# RS485_MODBUS.net
KiCad netlist of a schematic drawn in Altium Designer
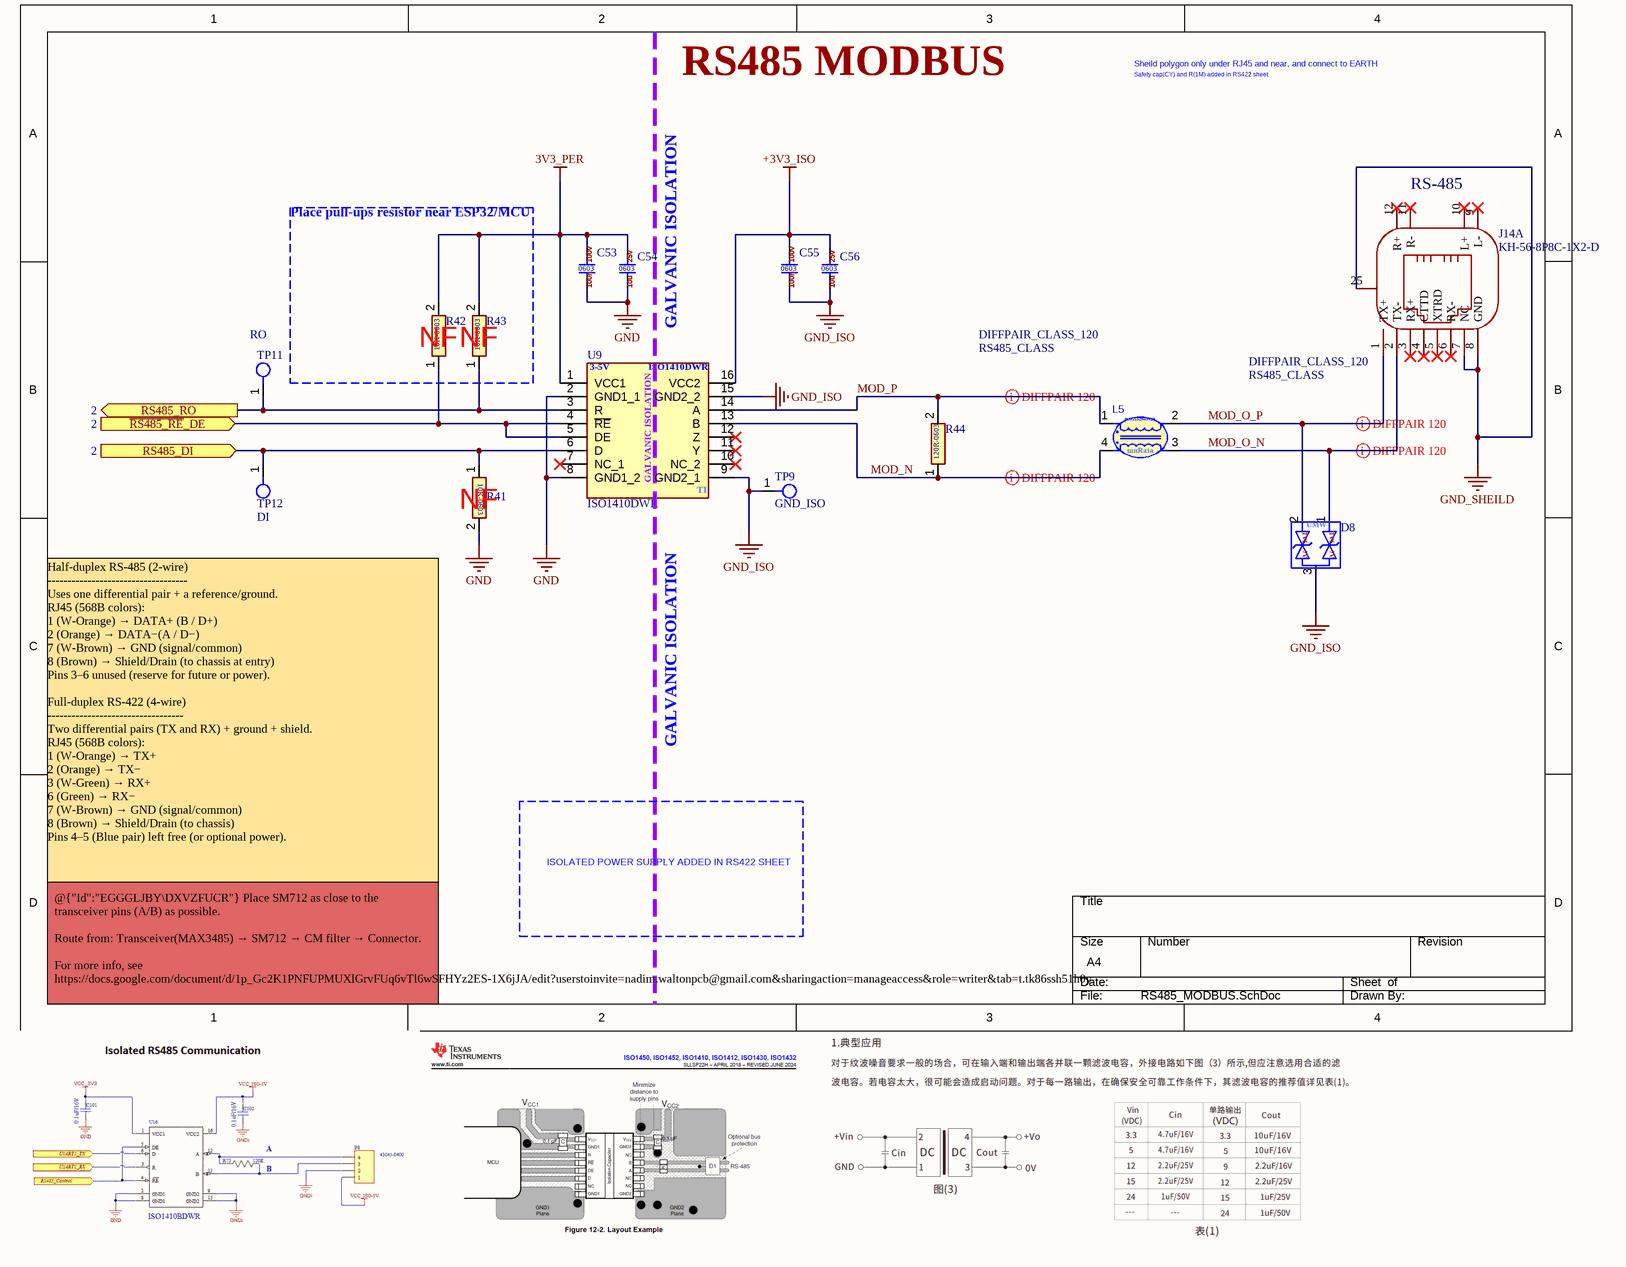
[diagram p0: RS485_MODBUS.SchDoc]

(export (version "E")
  (design (tool "Eeschema 10.0.6"))
  (components
    (comp (ref "C53")
      (value "CL10B104KC8NNNC")
      (footprint "0603-CAP")
      (description "CAP: CER 100NF 100V X7R 0603")
      (fields (field (name "LCSC PART #") "C15725"))
      (libsource (lib "Nadim Altium Lib-Univ") (part "CL10B104KC8NNNC"))
    )
    (comp (ref "C54")
      (value "CL10A106MA8NRNC")
      (footprint "0603-CAP")
      (description "CAP: CER 10UF 25V X5R 0603")
      (fields (field (name "LCSC PART #") "C96446"))
      (libsource (lib "Nadim Altium Lib-Univ") (part "CL10A106MA8NRNC"))
    )
    (comp (ref "C55")
      (value "CL10B104KC8NNNC")
      (footprint "0603-CAP")
      (description "CAP: CER 100NF 100V X7R 0603")
      (fields (field (name "LCSC PART #") "C15725"))
      (libsource (lib "Nadim Altium Lib-Univ") (part "CL10B104KC8NNNC"))
    )
    (comp (ref "C56")
      (value "CL10A106MA8NRNC")
      (footprint "0603-CAP")
      (description "CAP: CER 10UF 25V X5R 0603")
      (fields (field (name "LCSC PART #") "C96446"))
      (libsource (lib "Nadim Altium Lib-Univ") (part "CL10A106MA8NRNC"))
    )
    (comp (ref "D8")
      (value "SM712(UMW)")
      (footprint "SOT-23-3")
      (description "DIODE TVS: 7V WM 11VC Voltage - Breakdown (Min) 6V\r\nSOT-23")
      (fields (field (name "LCSC PART #") "C7436899"))
      (libsource (lib "Nadim Altium Lib-Univ") (part "SM712(UMW)"))
    )
    (comp (ref "J14")
      (value "KH-56-8P8C-1X2-D")
      (footprint "RJ45-TH_KH-56-8P8C-1X2-D")
      (fields (field (name "LCSC PART #") "C2828088"))
      (libsource (lib "Nadim Altium Lib-Univ") (part "KH-56-8P8C-1X2-D_1"))
    )
    (comp (ref "L5")
      (value "DLW21SZ900HQ2L")
      (footprint "FILTER-SMD_4P-L2.0-W1.2-BL_DLW21H")
      (description "Filter CM: 90Ω@100MHz 410mΩ 2 0805 Common Mode Filters ROHS")
      (fields (field (name "LCSC PART #") "C161093"))
      (libsource (lib "Nadim Altium Lib-Univ") (part "DLW21SZ900HQ2L"))
    )
    (comp (ref "R41")
      (value "0603WAF1002T5E")
      (footprint "0603-RES")
      (description "RES: 10K OHM 1% 100mW 0603 75V")
      (fields (field (name "LCSC PART #") "C25804"))
      (libsource (lib "") (part "0603WAF1002T5E_1"))
    )
    (comp (ref "R42")
      (value "0603WAF1002T5E")
      (footprint "0603-RES")
      (description "RES: 10K OHM 1% 100mW 0603 75V")
      (fields (field (name "LCSC PART #") "C25804"))
      (libsource (lib "Nadim Altium Lib-Univ") (part "0603WAF1002T5E"))
    )
    (comp (ref "R43")
      (value "0603WAF1002T5E")
      (footprint "0603-RES")
      (description "RES: 10K OHM 1% 100mW 0603 75V")
      (fields (field (name "LCSC PART #") "C25804"))
      (libsource (lib "Nadim Altium Lib-Univ") (part "0603WAF1002T5E"))
    )
    (comp (ref "R44")
      (value "0603WAF1200T5E")
      (footprint "0603-RES")
      (description "RES: 120R OHM 1% 100mW 0603 75V")
      (fields (field (name "LCSC PART #") "C22787"))
      (libsource (lib "Nadim Altium Lib-Univ") (part "0603WAF1200T5E"))
    )
    (comp (ref "TP9")
      (value "GND_ISO")
      (footprint "Test Pad FP")
      (description "TESTPAD: Test Pad")
      (libsource (lib "Nadim Altium Lib-Univ") (part "Test Pad"))
    )
    (comp (ref "TP11")
      (value "RO")
      (footprint "Test Pad FP")
      (description "TESTPAD: Test Pad")
      (libsource (lib "Nadim Altium Lib-Univ") (part "Test Pad"))
    )
    (comp (ref "TP12")
      (value "DI")
      (footprint "Test Pad FP")
      (description "TESTPAD: Test Pad")
      (libsource (lib "Nadim Altium Lib-Univ") (part "Test Pad"))
    )
    (comp (ref "U9")
      (value "ISO1410DWR")
      (footprint "Nadim Altium Lib-Univ:SOIC-16-300mil")
      (description "MODBUS: Galvanic Isolated 3-5V Full and Half-Duplex RS-485 RS-422 Transceivers")
      (fields (field (name "LCSC PART #") "C2671566"))
      (libsource (lib "Nadim Altium Lib-Univ") (part "ISO1410DWR"))
    )
  )
  (nets
    (net (code "1") (name "+3V3_ISO") (class "Default")
      (node (ref "C55") (pin "2") (pinfunction "2_2") (pintype "passive"))
      (node (ref "C56") (pin "2") (pinfunction "2_2") (pintype "passive"))
      (node (ref "U9") (pin "16") (pinfunction "VCC2_16") (pintype "passive"))
    )
    (net (code "2") (name "/MOD_N") (class "Default")
      (node (ref "L5") (pin "4") (pinfunction "4_4") (pintype "passive"))
      (node (ref "R44") (pin "1") (pinfunction "1_1") (pintype "passive"))
      (node (ref "U9") (pin "13") (pinfunction "B_13") (pintype "passive"))
    )
    (net (code "3") (name "/MOD_O_N") (class "Default")
      (node (ref "D8") (pin "1") (pinfunction "1_1") (pintype "passive"))
      (node (ref "J14") (pin "2") (pinfunction "TX-_2") (pintype "passive"))
      (node (ref "L5") (pin "3") (pinfunction "3_3") (pintype "passive"))
    )
    (net (code "4") (name "/MOD_O_P") (class "Default")
      (node (ref "D8") (pin "2") (pinfunction "2_2") (pintype "passive"))
      (node (ref "J14") (pin "1") (pinfunction "TX+_1") (pintype "passive"))
      (node (ref "L5") (pin "2") (pinfunction "2_2") (pintype "passive"))
    )
    (net (code "5") (name "/MOD_P") (class "Default")
      (node (ref "L5") (pin "1") (pinfunction "1_1") (pintype "passive"))
      (node (ref "R44") (pin "2") (pinfunction "2_2") (pintype "passive"))
      (node (ref "U9") (pin "14") (pinfunction "A_14") (pintype "passive"))
    )
    (net (code "6") (name "/RS485_DI") (class "Default")
      (node (ref "R41") (pin "1") (pinfunction "1_1") (pintype "passive"))
      (node (ref "TP12") (pin "1") (pinfunction "1_1") (pintype "passive"))
      (node (ref "U9") (pin "6") (pinfunction "D_6") (pintype "passive"))
    )
    (net (code "7") (name "/RS485_RO") (class "Default")
      (node (ref "R43") (pin "1") (pinfunction "1_1") (pintype "passive"))
      (node (ref "TP11") (pin "1") (pinfunction "1_1") (pintype "passive"))
      (node (ref "U9") (pin "3") (pinfunction "R_3") (pintype "passive"))
    )
    (net (code "8") (name "/~{RS485_RE}_DE") (class "Default")
      (node (ref "R42") (pin "1") (pinfunction "1_1") (pintype "passive"))
      (node (ref "U9") (pin "4") (pinfunction "~{RE}_4") (pintype "passive"))
      (node (ref "U9") (pin "5") (pinfunction "DE_5") (pintype "passive"))
    )
    (net (code "9") (name "3V3_PER") (class "Default")
      (node (ref "C53") (pin "2") (pinfunction "2_2") (pintype "passive"))
      (node (ref "C54") (pin "2") (pinfunction "2_2") (pintype "passive"))
      (node (ref "R42") (pin "2") (pinfunction "2_2") (pintype "passive"))
      (node (ref "R43") (pin "2") (pinfunction "2_2") (pintype "passive"))
      (node (ref "U9") (pin "1") (pinfunction "VCC1_1") (pintype "passive"))
    )
    (net (code "10") (name "GND") (class "Default")
      (node (ref "C53") (pin "1") (pinfunction "1_1") (pintype "passive"))
      (node (ref "C54") (pin "1") (pinfunction "1_1") (pintype "passive"))
      (node (ref "R41") (pin "2") (pinfunction "2_2") (pintype "passive"))
      (node (ref "U9") (pin "2") (pinfunction "GND1_1_2") (pintype "passive"))
      (node (ref "U9") (pin "8") (pinfunction "GND1_2_8") (pintype "passive"))
    )
    (net (code "11") (name "GND_ISO") (class "Default")
      (node (ref "C55") (pin "1") (pinfunction "1_1") (pintype "passive"))
      (node (ref "C56") (pin "1") (pinfunction "1_1") (pintype "passive"))
      (node (ref "D8") (pin "3") (pinfunction "3_3") (pintype "passive"))
      (node (ref "TP9") (pin "1") (pinfunction "1_1") (pintype "passive"))
      (node (ref "U9") (pin "15") (pinfunction "GND2_2_15") (pintype "passive"))
      (node (ref "U9") (pin "9") (pinfunction "GND2_1_9") (pintype "passive"))
    )
    (net (code "12") (name "GND_SHEILD") (class "Default")
      (node (ref "J14") (pin "25") (pinfunction "SHELL_25") (pintype "passive"))
      (node (ref "J14") (pin "7") (pinfunction "NC_7") (pintype "passive"))
      (node (ref "J14") (pin "8") (pinfunction "GND_8") (pintype "passive"))
    )
    (net (code "13") (name "unconnected-(J14A-CTTD-Pad4)") (class "Default")
      (node (ref "J14") (pin "4") (pinfunction "CTTD_4") (pintype "passive+no_connect"))
    )
    (net (code "14") (name "unconnected-(J14A-L+-Pad10)") (class "Default")
      (node (ref "J14") (pin "10") (pinfunction "L+_10") (pintype "passive+no_connect"))
    )
    (net (code "15") (name "unconnected-(J14A-L--Pad9)") (class "Default")
      (node (ref "J14") (pin "9") (pinfunction "L-_9") (pintype "passive+no_connect"))
    )
    (net (code "16") (name "unconnected-(J14A-R+-Pad12)") (class "Default")
      (node (ref "J14") (pin "12") (pinfunction "R+_12") (pintype "passive+no_connect"))
    )
    (net (code "17") (name "unconnected-(J14A-R--Pad11)") (class "Default")
      (node (ref "J14") (pin "11") (pinfunction "R-_11") (pintype "passive+no_connect"))
    )
    (net (code "18") (name "unconnected-(J14A-RX+-Pad3)") (class "Default")
      (node (ref "J14") (pin "3") (pinfunction "RX+_3") (pintype "passive+no_connect"))
    )
    (net (code "19") (name "unconnected-(J14A-RX--Pad6)") (class "Default")
      (node (ref "J14") (pin "6") (pinfunction "RX-_6") (pintype "passive+no_connect"))
    )
    (net (code "20") (name "unconnected-(J14A-XTRD-Pad5)") (class "Default")
      (node (ref "J14") (pin "5") (pinfunction "XTRD_5") (pintype "passive+no_connect"))
    )
    (net (code "21") (name "unconnected-(U9-NC_1-Pad7)") (class "Default")
      (node (ref "U9") (pin "7") (pinfunction "NC_1_7") (pintype "passive+no_connect"))
    )
    (net (code "22") (name "unconnected-(U9-NC_2-Pad10)") (class "Default")
      (node (ref "U9") (pin "10") (pinfunction "NC_2_10") (pintype "passive+no_connect"))
    )
    (net (code "23") (name "unconnected-(U9-Y-Pad11)") (class "Default")
      (node (ref "U9") (pin "11") (pinfunction "Y_11") (pintype "passive+no_connect"))
    )
    (net (code "24") (name "unconnected-(U9-Z-Pad12)") (class "Default")
      (node (ref "U9") (pin "12") (pinfunction "Z_12") (pintype "passive+no_connect"))
    )
  )
)
